# LEOPAD.net
KiCad netlist of a schematic drawn in EAGLE
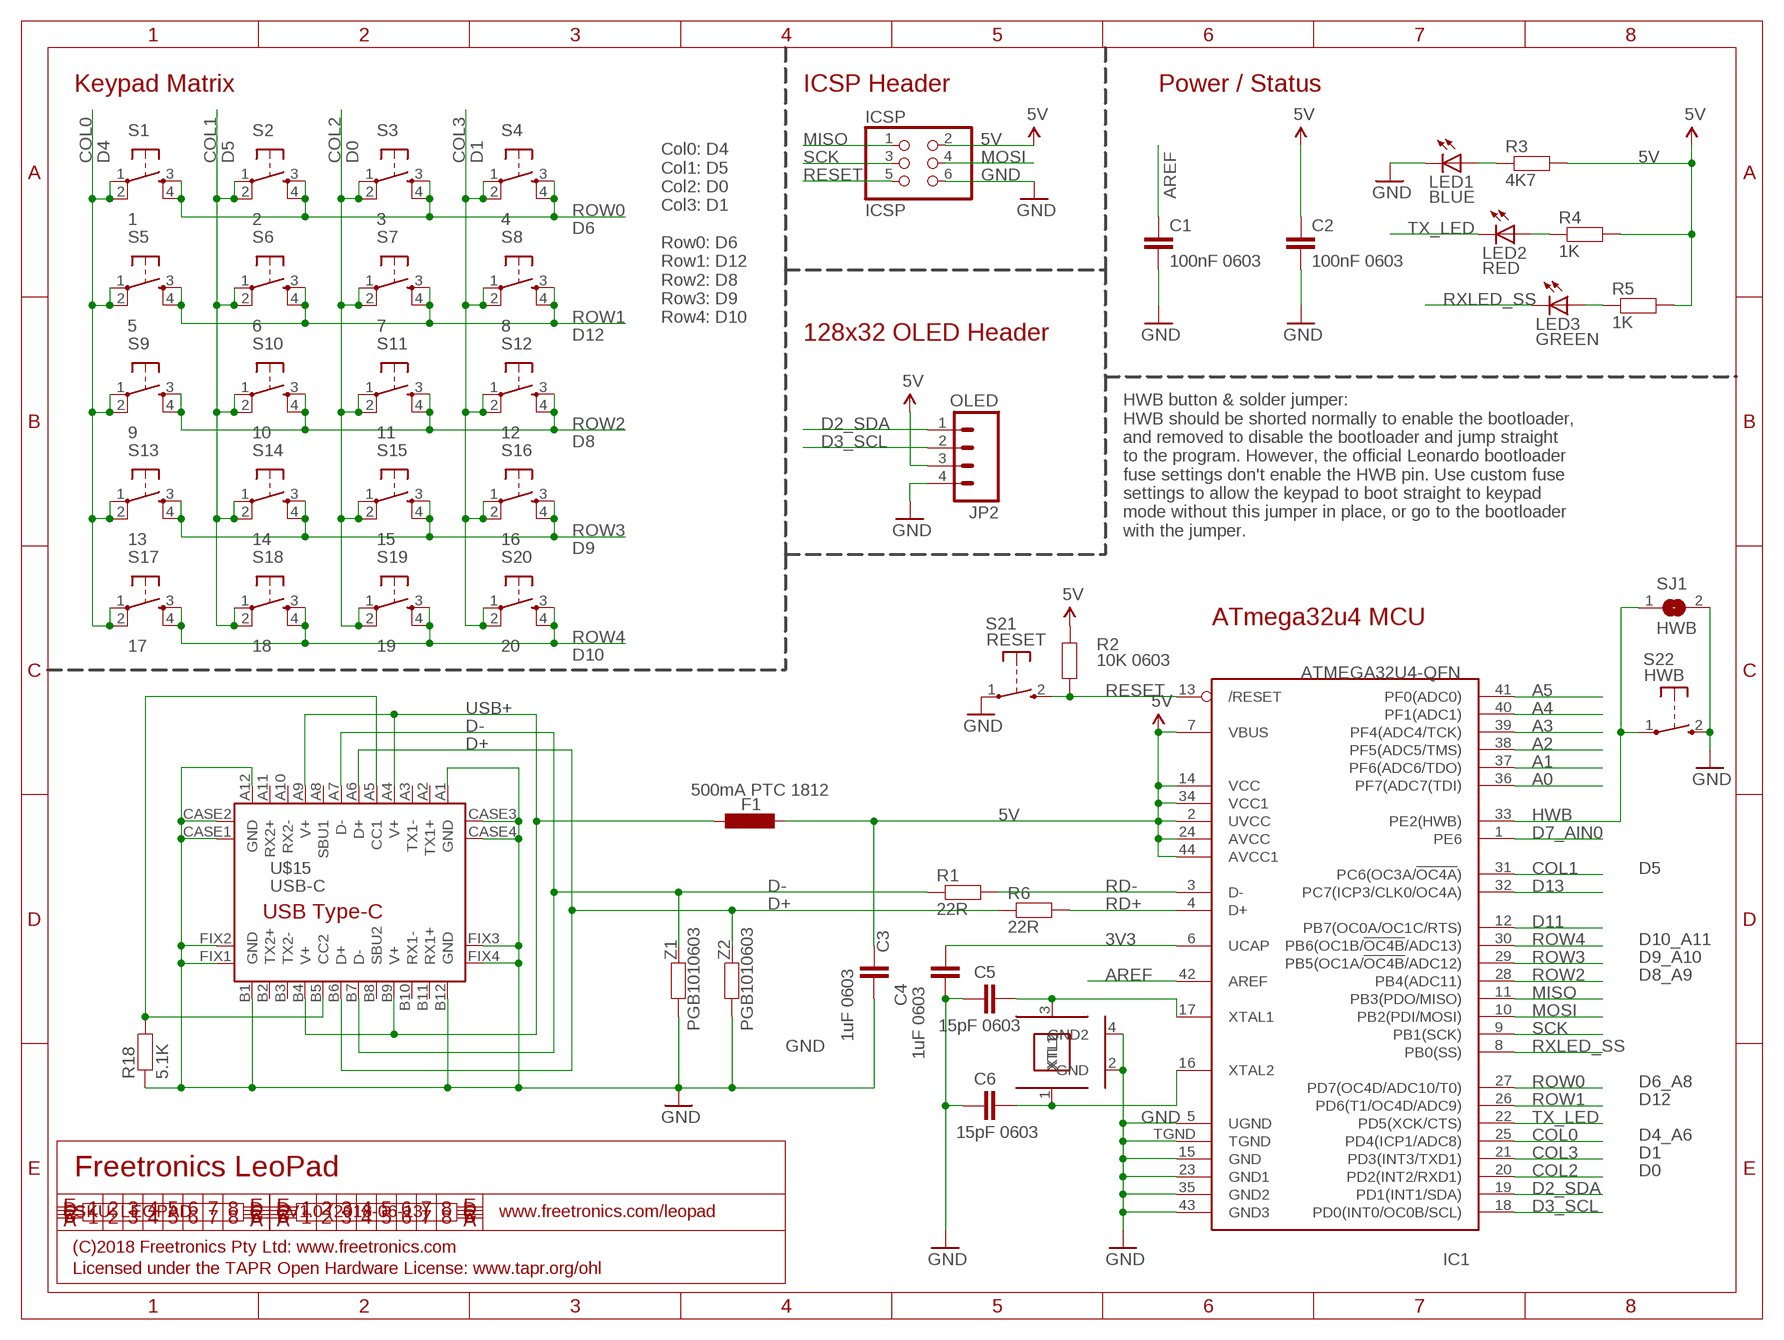
[diagram p0: schematic, sheet 1]

(export (version "E")
  (design (tool "Eeschema 10.0.6"))
  (components
    (comp (ref "C1")
      (value "100nF 0603")
      (footprint "eagle-import:0603")
      (libsource (lib "eagle-import") (part "CAP0603"))
    )
    (comp (ref "C2")
      (value "100nF 0603")
      (footprint "eagle-import:0603")
      (libsource (lib "eagle-import") (part "CAP0603"))
    )
    (comp (ref "C3")
      (value "1uF 0603")
      (footprint "eagle-import:0603")
      (libsource (lib "eagle-import") (part "CAP0603"))
    )
    (comp (ref "C4")
      (value "1uF 0603")
      (footprint "eagle-import:0603")
      (libsource (lib "eagle-import") (part "CAP0603"))
    )
    (comp (ref "C5")
      (value "15pF 0603")
      (footprint "eagle-import:0603")
      (libsource (lib "eagle-import") (part "CAP0603"))
    )
    (comp (ref "C6")
      (value "15pF 0603")
      (footprint "eagle-import:0603")
      (libsource (lib "eagle-import") (part "CAP0603"))
    )
    (comp (ref "F1")
      (value "500mA PTC 1812")
      (footprint "eagle-import:L1812")
      (libsource (lib "eagle-import") (part "L-EUL1812"))
    )
    (comp (ref "IC1")
      (value "ATMEGA32U4-QFN")
      (footprint "eagle-import:QFN-44N")
      (libsource (lib "eagle-import") (part "ATMEGA32U4-QFN"))
    )
    (comp (ref "ICSP")
      (value "ICSP")
      (footprint "eagle-import:2X03")
      (libsource (lib "eagle-import") (part "PINHD-2X3"))
    )
    (comp (ref "JP2")
      (value "OLED")
      (footprint "eagle-import:1X04")
      (libsource (lib "eagle-import") (part "M04PTH"))
    )
    (comp (ref "LED1")
      (value "BLUE")
      (footprint "eagle-import:LED-0603")
      (libsource (lib "eagle-import") (part "LED0603"))
    )
    (comp (ref "LED2")
      (value "RED")
      (footprint "eagle-import:LED-0603")
      (libsource (lib "eagle-import") (part "LED0603"))
    )
    (comp (ref "LED3")
      (value "GREEN")
      (footprint "eagle-import:LED-0603")
      (libsource (lib "eagle-import") (part "LED0603"))
    )
    (comp (ref "R1")
      (value "22R")
      (footprint "eagle-import:0603")
      (libsource (lib "eagle-import") (part "RESISTOR0603"))
    )
    (comp (ref "R2")
      (value "10K 0603")
      (footprint "eagle-import:0603")
      (libsource (lib "eagle-import") (part "freetronics-master-v1.1_RESISTOR0603"))
    )
    (comp (ref "R3")
      (value "4K7")
      (footprint "eagle-import:0603")
      (libsource (lib "eagle-import") (part "RESISTOR0603"))
    )
    (comp (ref "R4")
      (value "1K")
      (footprint "eagle-import:0603")
      (libsource (lib "eagle-import") (part "RESISTOR0603"))
    )
    (comp (ref "R5")
      (value "1K")
      (footprint "eagle-import:0603")
      (libsource (lib "eagle-import") (part "RESISTOR0603"))
    )
    (comp (ref "R6")
      (value "22R")
      (footprint "eagle-import:0603")
      (libsource (lib "eagle-import") (part "RESISTOR0603"))
    )
    (comp (ref "R18")
      (value "5.1K")
      (footprint "eagle-import:0603")
      (libsource (lib "eagle-import") (part "freetronics-original_RESISTOR0603"))
    )
    (comp (ref "S1")
      (value "1")
      (footprint "eagle-import:TACTILE-PTH-12MM")
      (libsource (lib "eagle-import") (part "TAC_SWITCH12"))
    )
    (comp (ref "S2")
      (value "2")
      (footprint "eagle-import:TACTILE-PTH-12MM")
      (libsource (lib "eagle-import") (part "TAC_SWITCH12"))
    )
    (comp (ref "S3")
      (value "3")
      (footprint "eagle-import:TACTILE-PTH-12MM")
      (libsource (lib "eagle-import") (part "TAC_SWITCH12"))
    )
    (comp (ref "S4")
      (value "4")
      (footprint "eagle-import:TACTILE-PTH-12MM")
      (libsource (lib "eagle-import") (part "TAC_SWITCH12"))
    )
    (comp (ref "S5")
      (value "5")
      (footprint "eagle-import:TACTILE-PTH-12MM")
      (libsource (lib "eagle-import") (part "TAC_SWITCH12"))
    )
    (comp (ref "S6")
      (value "6")
      (footprint "eagle-import:TACTILE-PTH-12MM")
      (libsource (lib "eagle-import") (part "TAC_SWITCH12"))
    )
    (comp (ref "S7")
      (value "7")
      (footprint "eagle-import:TACTILE-PTH-12MM")
      (libsource (lib "eagle-import") (part "TAC_SWITCH12"))
    )
    (comp (ref "S8")
      (value "8")
      (footprint "eagle-import:TACTILE-PTH-12MM")
      (libsource (lib "eagle-import") (part "TAC_SWITCH12"))
    )
    (comp (ref "S9")
      (value "9")
      (footprint "eagle-import:TACTILE-PTH-12MM")
      (libsource (lib "eagle-import") (part "TAC_SWITCH12"))
    )
    (comp (ref "S10")
      (value "10")
      (footprint "eagle-import:TACTILE-PTH-12MM")
      (libsource (lib "eagle-import") (part "TAC_SWITCH12"))
    )
    (comp (ref "S11")
      (value "11")
      (footprint "eagle-import:TACTILE-PTH-12MM")
      (libsource (lib "eagle-import") (part "TAC_SWITCH12"))
    )
    (comp (ref "S12")
      (value "12")
      (footprint "eagle-import:TACTILE-PTH-12MM")
      (libsource (lib "eagle-import") (part "TAC_SWITCH12"))
    )
    (comp (ref "S13")
      (value "13")
      (footprint "eagle-import:TACTILE-PTH-12MM")
      (libsource (lib "eagle-import") (part "TAC_SWITCH12"))
    )
    (comp (ref "S14")
      (value "14")
      (footprint "eagle-import:TACTILE-PTH-12MM")
      (libsource (lib "eagle-import") (part "TAC_SWITCH12"))
    )
    (comp (ref "S15")
      (value "15")
      (footprint "eagle-import:TACTILE-PTH-12MM")
      (libsource (lib "eagle-import") (part "TAC_SWITCH12"))
    )
    (comp (ref "S16")
      (value "16")
      (footprint "eagle-import:TACTILE-PTH-12MM")
      (libsource (lib "eagle-import") (part "TAC_SWITCH12"))
    )
    (comp (ref "S17")
      (value "17")
      (footprint "eagle-import:TACTILE-PTH-12MM")
      (libsource (lib "eagle-import") (part "TAC_SWITCH12"))
    )
    (comp (ref "S18")
      (value "18")
      (footprint "eagle-import:TACTILE-PTH-12MM")
      (libsource (lib "eagle-import") (part "TAC_SWITCH12"))
    )
    (comp (ref "S19")
      (value "19")
      (footprint "eagle-import:TACTILE-PTH-12MM")
      (libsource (lib "eagle-import") (part "TAC_SWITCH12"))
    )
    (comp (ref "S20")
      (value "20")
      (footprint "eagle-import:TACTILE-PTH-12MM")
      (libsource (lib "eagle-import") (part "TAC_SWITCH12"))
    )
    (comp (ref "S21")
      (value "RESET")
      (footprint "eagle-import:TACTILE_SWITCH_SMD_2PIN_TINY")
      (libsource (lib "eagle-import") (part "TAC_SWITCH_2PINSMT"))
    )
    (comp (ref "S22")
      (value "HWB")
      (footprint "eagle-import:TACTILE_SWITCH_SMD_2PIN_TINY")
      (libsource (lib "eagle-import") (part "TAC_SWITCH_2PINSMT"))
    )
    (comp (ref "SJ1")
      (value "HWB")
      (footprint "eagle-import:SJ")
      (libsource (lib "eagle-import") (part "SJN"))
    )
    (comp (ref "U$15")
      (value "USB-C")
      (footprint "eagle-import:USB-C-U52A")
      (libsource (lib "eagle-import") (part "USB-C"))
    )
    (comp (ref "XTL1")
      (value "16MHz")
      (footprint "eagle-import:CRYSTAL-SMD-3X2")
      (libsource (lib "eagle-import") (part "CRYSTAL-GND3X2"))
    )
    (comp (ref "Z1")
      (value "PGB1010603")
      (footprint "eagle-import:0603")
      (libsource (lib "eagle-import") (part "freetronics-master-v1.1_RESISTOR0603"))
    )
    (comp (ref "Z2")
      (value "PGB1010603")
      (footprint "eagle-import:0603")
      (libsource (lib "eagle-import") (part "freetronics-master-v1.1_RESISTOR0603"))
    )
  )
  (nets
    (net (code "1") (name "/3V3") (class "Default")
      (node (ref "C4") (pin "2") (pinfunction "2_2") (pintype "passive"))
      (node (ref "IC1") (pin "6") (pinfunction "UCAP_6") (pintype "bidirectional"))
    )
    (net (code "2") (name "/A0") (class "Default")
      (node (ref "IC1") (pin "36") (pinfunction "PF7(ADC7(TDI)_36") (pintype "bidirectional"))
    )
    (net (code "3") (name "/A1") (class "Default")
      (node (ref "IC1") (pin "37") (pinfunction "PF6(ADC6/TDO)_37") (pintype "bidirectional"))
    )
    (net (code "4") (name "/A2") (class "Default")
      (node (ref "IC1") (pin "38") (pinfunction "PF5(ADC5/TMS)_38") (pintype "bidirectional"))
    )
    (net (code "5") (name "/A3") (class "Default")
      (node (ref "IC1") (pin "39") (pinfunction "PF4(ADC4/TCK)_39") (pintype "bidirectional"))
    )
    (net (code "6") (name "/A4") (class "Default")
      (node (ref "IC1") (pin "40") (pinfunction "PF1(ADC1)_40") (pintype "bidirectional"))
    )
    (net (code "7") (name "/A5") (class "Default")
      (node (ref "IC1") (pin "41") (pinfunction "PF0(ADC0)_41") (pintype "bidirectional"))
    )
    (net (code "8") (name "/AREF") (class "Default")
      (node (ref "C1") (pin "1") (pinfunction "1_1") (pintype "passive"))
      (node (ref "IC1") (pin "42") (pinfunction "AREF_42") (pintype "bidirectional"))
    )
    (net (code "9") (name "/COL0") (class "Default")
      (node (ref "IC1") (pin "25") (pinfunction "PD4(ICP1/ADC8)_25") (pintype "bidirectional"))
      (node (ref "S1") (pin "1") (pinfunction "1_1") (pintype "passive"))
      (node (ref "S1") (pin "2") (pinfunction "2_2") (pintype "passive"))
      (node (ref "S13") (pin "1") (pinfunction "1_1") (pintype "passive"))
      (node (ref "S13") (pin "2") (pinfunction "2_2") (pintype "passive"))
      (node (ref "S17") (pin "1") (pinfunction "1_1") (pintype "passive"))
      (node (ref "S17") (pin "2") (pinfunction "2_2") (pintype "passive"))
      (node (ref "S5") (pin "1") (pinfunction "1_1") (pintype "passive"))
      (node (ref "S5") (pin "2") (pinfunction "2_2") (pintype "passive"))
      (node (ref "S9") (pin "1") (pinfunction "1_1") (pintype "passive"))
      (node (ref "S9") (pin "2") (pinfunction "2_2") (pintype "passive"))
    )
    (net (code "10") (name "/COL1") (class "Default")
      (node (ref "IC1") (pin "31") (pinfunction "PC6(OC3A/~{OC4A})_31") (pintype "bidirectional"))
      (node (ref "S10") (pin "1") (pinfunction "1_1") (pintype "passive"))
      (node (ref "S10") (pin "2") (pinfunction "2_2") (pintype "passive"))
      (node (ref "S14") (pin "1") (pinfunction "1_1") (pintype "passive"))
      (node (ref "S14") (pin "2") (pinfunction "2_2") (pintype "passive"))
      (node (ref "S18") (pin "1") (pinfunction "1_1") (pintype "passive"))
      (node (ref "S18") (pin "2") (pinfunction "2_2") (pintype "passive"))
      (node (ref "S2") (pin "1") (pinfunction "1_1") (pintype "passive"))
      (node (ref "S2") (pin "2") (pinfunction "2_2") (pintype "passive"))
      (node (ref "S6") (pin "1") (pinfunction "1_1") (pintype "passive"))
      (node (ref "S6") (pin "2") (pinfunction "2_2") (pintype "passive"))
    )
    (net (code "11") (name "/COL2") (class "Default")
      (node (ref "IC1") (pin "20") (pinfunction "PD2(INT2/RXD1)_20") (pintype "bidirectional"))
      (node (ref "S11") (pin "1") (pinfunction "1_1") (pintype "passive"))
      (node (ref "S11") (pin "2") (pinfunction "2_2") (pintype "passive"))
      (node (ref "S15") (pin "1") (pinfunction "1_1") (pintype "passive"))
      (node (ref "S15") (pin "2") (pinfunction "2_2") (pintype "passive"))
      (node (ref "S19") (pin "1") (pinfunction "1_1") (pintype "passive"))
      (node (ref "S19") (pin "2") (pinfunction "2_2") (pintype "passive"))
      (node (ref "S3") (pin "1") (pinfunction "1_1") (pintype "passive"))
      (node (ref "S3") (pin "2") (pinfunction "2_2") (pintype "passive"))
      (node (ref "S7") (pin "1") (pinfunction "1_1") (pintype "passive"))
      (node (ref "S7") (pin "2") (pinfunction "2_2") (pintype "passive"))
    )
    (net (code "12") (name "/COL3") (class "Default")
      (node (ref "IC1") (pin "21") (pinfunction "PD3(INT3/TXD1)_21") (pintype "bidirectional"))
      (node (ref "S12") (pin "1") (pinfunction "1_1") (pintype "passive"))
      (node (ref "S12") (pin "2") (pinfunction "2_2") (pintype "passive"))
      (node (ref "S16") (pin "1") (pinfunction "1_1") (pintype "passive"))
      (node (ref "S16") (pin "2") (pinfunction "2_2") (pintype "passive"))
      (node (ref "S20") (pin "1") (pinfunction "1_1") (pintype "passive"))
      (node (ref "S20") (pin "2") (pinfunction "2_2") (pintype "passive"))
      (node (ref "S4") (pin "1") (pinfunction "1_1") (pintype "passive"))
      (node (ref "S4") (pin "2") (pinfunction "2_2") (pintype "passive"))
      (node (ref "S8") (pin "1") (pinfunction "1_1") (pintype "passive"))
      (node (ref "S8") (pin "2") (pinfunction "2_2") (pintype "passive"))
    )
    (net (code "13") (name "/D+") (class "Default")
      (node (ref "R6") (pin "1") (pinfunction "1_1") (pintype "passive"))
      (node (ref "U$15") (pin "A6") (pinfunction "D+_A6") (pintype "bidirectional"))
      (node (ref "U$15") (pin "B6") (pinfunction "D+_B6") (pintype "bidirectional"))
      (node (ref "Z2") (pin "2") (pinfunction "2_2") (pintype "passive"))
    )
    (net (code "14") (name "/D-") (class "Default")
      (node (ref "R1") (pin "1") (pinfunction "1_1") (pintype "passive"))
      (node (ref "U$15") (pin "A7") (pinfunction "D-_A7") (pintype "bidirectional"))
      (node (ref "U$15") (pin "B7") (pinfunction "D-_B7") (pintype "bidirectional"))
      (node (ref "Z1") (pin "2") (pinfunction "2_2") (pintype "passive"))
    )
    (net (code "15") (name "/D2_SDA") (class "Default")
      (node (ref "IC1") (pin "19") (pinfunction "PD1(INT1/SDA)_19") (pintype "bidirectional"))
      (node (ref "JP2") (pin "1") (pinfunction "1_1") (pintype "passive"))
    )
    (net (code "16") (name "/D3_SCL") (class "Default")
      (node (ref "IC1") (pin "18") (pinfunction "PD0(INT0/OC0B/SCL)_18") (pintype "bidirectional"))
      (node (ref "JP2") (pin "2") (pinfunction "2_2") (pintype "passive"))
    )
    (net (code "17") (name "/D7_AIN0") (class "Default")
      (node (ref "IC1") (pin "1") (pinfunction "PE6_1") (pintype "bidirectional"))
    )
    (net (code "18") (name "/D11") (class "Default")
      (node (ref "IC1") (pin "12") (pinfunction "PB7(OC0A/OC1C/RTS)_12") (pintype "bidirectional"))
    )
    (net (code "19") (name "/D13") (class "Default")
      (node (ref "IC1") (pin "32") (pinfunction "PC7(ICP3/CLK0/OC4A)_32") (pintype "bidirectional"))
    )
    (net (code "20") (name "/HWB") (class "Default")
      (node (ref "IC1") (pin "33") (pinfunction "PE2(HWB)_33") (pintype "bidirectional"))
      (node (ref "S22") (pin "1") (pinfunction "P_1") (pintype "passive"))
      (node (ref "SJ1") (pin "1") (pinfunction "1_1") (pintype "passive"))
    )
    (net (code "21") (name "/MISO") (class "Default")
      (node (ref "IC1") (pin "11") (pinfunction "PB3(PDO/MISO)_11") (pintype "bidirectional"))
      (node (ref "ICSP") (pin "1") (pinfunction "1_1") (pintype "passive"))
    )
    (net (code "22") (name "/MOSI") (class "Default")
      (node (ref "IC1") (pin "10") (pinfunction "PB2(PDI/MOSI)_10") (pintype "bidirectional"))
      (node (ref "ICSP") (pin "4") (pinfunction "4_4") (pintype "passive"))
    )
    (net (code "23") (name "/RD+") (class "Default")
      (node (ref "IC1") (pin "4") (pinfunction "D+_4") (pintype "bidirectional"))
      (node (ref "R6") (pin "2") (pinfunction "2_2") (pintype "passive"))
    )
    (net (code "24") (name "/RD-") (class "Default")
      (node (ref "IC1") (pin "3") (pinfunction "D-_3") (pintype "bidirectional"))
      (node (ref "R1") (pin "2") (pinfunction "2_2") (pintype "passive"))
    )
    (net (code "25") (name "/RESET") (class "Default")
      (node (ref "IC1") (pin "13") (pinfunction "/RESET_13") (pintype "bidirectional"))
      (node (ref "ICSP") (pin "5") (pinfunction "5_5") (pintype "passive"))
      (node (ref "R2") (pin "1") (pinfunction "1_1") (pintype "passive"))
      (node (ref "S21") (pin "2") (pinfunction "S_2") (pintype "passive"))
    )
    (net (code "26") (name "/ROW0") (class "Default")
      (node (ref "IC1") (pin "27") (pinfunction "PD7(OC4D/ADC10/T0)_27") (pintype "bidirectional"))
      (node (ref "S1") (pin "3") (pinfunction "3_3") (pintype "passive"))
      (node (ref "S1") (pin "4") (pinfunction "4_4") (pintype "passive"))
      (node (ref "S2") (pin "3") (pinfunction "3_3") (pintype "passive"))
      (node (ref "S2") (pin "4") (pinfunction "4_4") (pintype "passive"))
      (node (ref "S3") (pin "3") (pinfunction "3_3") (pintype "passive"))
      (node (ref "S3") (pin "4") (pinfunction "4_4") (pintype "passive"))
      (node (ref "S4") (pin "3") (pinfunction "3_3") (pintype "passive"))
      (node (ref "S4") (pin "4") (pinfunction "4_4") (pintype "passive"))
    )
    (net (code "27") (name "/ROW1") (class "Default")
      (node (ref "IC1") (pin "26") (pinfunction "PD6(T1/OC4D/ADC9)_26") (pintype "bidirectional"))
      (node (ref "S5") (pin "3") (pinfunction "3_3") (pintype "passive"))
      (node (ref "S5") (pin "4") (pinfunction "4_4") (pintype "passive"))
      (node (ref "S6") (pin "3") (pinfunction "3_3") (pintype "passive"))
      (node (ref "S6") (pin "4") (pinfunction "4_4") (pintype "passive"))
      (node (ref "S7") (pin "3") (pinfunction "3_3") (pintype "passive"))
      (node (ref "S7") (pin "4") (pinfunction "4_4") (pintype "passive"))
      (node (ref "S8") (pin "3") (pinfunction "3_3") (pintype "passive"))
      (node (ref "S8") (pin "4") (pinfunction "4_4") (pintype "passive"))
    )
    (net (code "28") (name "/ROW2") (class "Default")
      (node (ref "IC1") (pin "28") (pinfunction "PB4(ADC11)_28") (pintype "bidirectional"))
      (node (ref "S10") (pin "3") (pinfunction "3_3") (pintype "passive"))
      (node (ref "S10") (pin "4") (pinfunction "4_4") (pintype "passive"))
      (node (ref "S11") (pin "3") (pinfunction "3_3") (pintype "passive"))
      (node (ref "S11") (pin "4") (pinfunction "4_4") (pintype "passive"))
      (node (ref "S12") (pin "3") (pinfunction "3_3") (pintype "passive"))
      (node (ref "S12") (pin "4") (pinfunction "4_4") (pintype "passive"))
      (node (ref "S9") (pin "3") (pinfunction "3_3") (pintype "passive"))
      (node (ref "S9") (pin "4") (pinfunction "4_4") (pintype "passive"))
    )
    (net (code "29") (name "/ROW3") (class "Default")
      (node (ref "IC1") (pin "29") (pinfunction "PB5(OC1A/~{OC4B}/ADC12)_29") (pintype "bidirectional"))
      (node (ref "S13") (pin "3") (pinfunction "3_3") (pintype "passive"))
      (node (ref "S13") (pin "4") (pinfunction "4_4") (pintype "passive"))
      (node (ref "S14") (pin "3") (pinfunction "3_3") (pintype "passive"))
      (node (ref "S14") (pin "4") (pinfunction "4_4") (pintype "passive"))
      (node (ref "S15") (pin "3") (pinfunction "3_3") (pintype "passive"))
      (node (ref "S15") (pin "4") (pinfunction "4_4") (pintype "passive"))
      (node (ref "S16") (pin "3") (pinfunction "3_3") (pintype "passive"))
      (node (ref "S16") (pin "4") (pinfunction "4_4") (pintype "passive"))
    )
    (net (code "30") (name "/ROW4") (class "Default")
      (node (ref "IC1") (pin "30") (pinfunction "PB6(OC1B/~{OC4B}/ADC13)_30") (pintype "bidirectional"))
      (node (ref "S17") (pin "3") (pinfunction "3_3") (pintype "passive"))
      (node (ref "S17") (pin "4") (pinfunction "4_4") (pintype "passive"))
      (node (ref "S18") (pin "3") (pinfunction "3_3") (pintype "passive"))
      (node (ref "S18") (pin "4") (pinfunction "4_4") (pintype "passive"))
      (node (ref "S19") (pin "3") (pinfunction "3_3") (pintype "passive"))
      (node (ref "S19") (pin "4") (pinfunction "4_4") (pintype "passive"))
      (node (ref "S20") (pin "3") (pinfunction "3_3") (pintype "passive"))
      (node (ref "S20") (pin "4") (pinfunction "4_4") (pintype "passive"))
    )
    (net (code "31") (name "/RXLED_SS") (class "Default")
      (node (ref "IC1") (pin "8") (pinfunction "PB0(SS)_8") (pintype "bidirectional"))
      (node (ref "LED3") (pin "C") (pinfunction "C_C") (pintype "passive"))
    )
    (net (code "32") (name "/SCK") (class "Default")
      (node (ref "IC1") (pin "9") (pinfunction "PB1(SCK)_9") (pintype "bidirectional"))
      (node (ref "ICSP") (pin "3") (pinfunction "3_3") (pintype "passive"))
    )
    (net (code "33") (name "/TX_LED") (class "Default")
      (node (ref "IC1") (pin "22") (pinfunction "PD5(XCK/CTS)_22") (pintype "bidirectional"))
      (node (ref "LED2") (pin "C") (pinfunction "C_C") (pintype "passive"))
    )
    (net (code "34") (name "/USB+") (class "Default")
      (node (ref "F1") (pin "1") (pinfunction "1_1") (pintype "passive"))
      (node (ref "U$15") (pin "A4") (pinfunction "V+_A4") (pintype "power_in"))
      (node (ref "U$15") (pin "A9") (pinfunction "V+_A9") (pintype "power_in"))
      (node (ref "U$15") (pin "B4") (pinfunction "V+_B4") (pintype "power_in"))
      (node (ref "U$15") (pin "B9") (pinfunction "V+_B9") (pintype "power_in"))
    )
    (net (code "35") (name "5V") (class "Default")
      (node (ref "C2") (pin "1") (pinfunction "1_1") (pintype "passive"))
      (node (ref "C3") (pin "1") (pinfunction "1_1") (pintype "passive"))
      (node (ref "F1") (pin "2") (pinfunction "2_2") (pintype "passive"))
      (node (ref "IC1") (pin "14") (pinfunction "VCC_14") (pintype "bidirectional"))
      (node (ref "IC1") (pin "2") (pinfunction "UVCC_2") (pintype "bidirectional"))
      (node (ref "IC1") (pin "24") (pinfunction "AVCC_24") (pintype "bidirectional"))
      (node (ref "IC1") (pin "34") (pinfunction "VCC1_34") (pintype "bidirectional"))
      (node (ref "IC1") (pin "44") (pinfunction "AVCC1_44") (pintype "bidirectional"))
      (node (ref "IC1") (pin "7") (pinfunction "VBUS_7") (pintype "bidirectional"))
      (node (ref "ICSP") (pin "2") (pinfunction "2_2") (pintype "passive"))
      (node (ref "JP2") (pin "3") (pinfunction "3_3") (pintype "passive"))
      (node (ref "R2") (pin "2") (pinfunction "2_2") (pintype "passive"))
      (node (ref "R3") (pin "2") (pinfunction "2_2") (pintype "passive"))
      (node (ref "R4") (pin "2") (pinfunction "2_2") (pintype "passive"))
      (node (ref "R5") (pin "2") (pinfunction "2_2") (pintype "passive"))
    )
    (net (code "36") (name "GND") (class "Default")
      (node (ref "C1") (pin "2") (pinfunction "2_2") (pintype "passive"))
      (node (ref "C2") (pin "2") (pinfunction "2_2") (pintype "passive"))
      (node (ref "C3") (pin "2") (pinfunction "2_2") (pintype "passive"))
      (node (ref "C4") (pin "1") (pinfunction "1_1") (pintype "passive"))
      (node (ref "C5") (pin "1") (pinfunction "1_1") (pintype "passive"))
      (node (ref "C6") (pin "1") (pinfunction "1_1") (pintype "passive"))
      (node (ref "IC1") (pin "15") (pinfunction "GND_15") (pintype "bidirectional"))
      (node (ref "IC1") (pin "23") (pinfunction "GND1_23") (pintype "bidirectional"))
      (node (ref "IC1") (pin "35") (pinfunction "GND2_35") (pintype "bidirectional"))
      (node (ref "IC1") (pin "43") (pinfunction "GND3_43") (pintype "bidirectional"))
      (node (ref "IC1") (pin "5") (pinfunction "UGND_5") (pintype "bidirectional"))
      (node (ref "IC1") (pin "TGND") (pinfunction "TGND_TGND") (pintype "bidirectional"))
      (node (ref "ICSP") (pin "6") (pinfunction "6_6") (pintype "passive"))
      (node (ref "JP2") (pin "4") (pinfunction "4_4") (pintype "passive"))
      (node (ref "LED1") (pin "C") (pinfunction "C_C") (pintype "passive"))
      (node (ref "R18") (pin "1") (pinfunction "1_1") (pintype "passive"))
      (node (ref "S21") (pin "1") (pinfunction "P_1") (pintype "passive"))
      (node (ref "S22") (pin "2") (pinfunction "S_2") (pintype "passive"))
      (node (ref "SJ1") (pin "2") (pinfunction "2_2") (pintype "passive"))
      (node (ref "U$15") (pin "A1") (pinfunction "GND_A1") (pintype "power_in"))
      (node (ref "U$15") (pin "A12") (pinfunction "GND_A12") (pintype "power_in"))
      (node (ref "U$15") (pin "B1") (pinfunction "GND_B1") (pintype "power_in"))
      (node (ref "U$15") (pin "B12") (pinfunction "GND_B12") (pintype "power_in"))
      (node (ref "U$15") (pin "CASE1") (pinfunction "GND_CASE1") (pintype "power_in"))
      (node (ref "U$15") (pin "CASE2") (pinfunction "GND_CASE2") (pintype "power_in"))
      (node (ref "U$15") (pin "CASE3") (pinfunction "GND_CASE3") (pintype "power_in"))
      (node (ref "U$15") (pin "CASE4") (pinfunction "GND_CASE4") (pintype "power_in"))
      (node (ref "U$15") (pin "FIX1") (pinfunction "GND_FIX1") (pintype "power_in"))
      (node (ref "U$15") (pin "FIX2") (pinfunction "GND_FIX2") (pintype "power_in"))
      (node (ref "U$15") (pin "FIX3") (pinfunction "GND_FIX3") (pintype "power_in"))
      (node (ref "U$15") (pin "FIX4") (pinfunction "GND_FIX4") (pintype "power_in"))
      (node (ref "XTL1") (pin "2") (pinfunction "GND_2") (pintype "bidirectional"))
      (node (ref "XTL1") (pin "4") (pinfunction "GND2_4") (pintype "bidirectional"))
      (node (ref "Z1") (pin "1") (pinfunction "1_1") (pintype "passive"))
      (node (ref "Z2") (pin "1") (pinfunction "1_1") (pintype "passive"))
    )
    (net (code "37") (name "Net-(IC1-XTAL1)") (class "Default")
      (node (ref "C5") (pin "2") (pinfunction "2_2") (pintype "passive"))
      (node (ref "IC1") (pin "17") (pinfunction "XTAL1_17") (pintype "bidirectional"))
      (node (ref "XTL1") (pin "3") (pinfunction "XTL2_3") (pintype "bidirectional"))
    )
    (net (code "38") (name "Net-(IC1-XTAL2)") (class "Default")
      (node (ref "C6") (pin "2") (pinfunction "2_2") (pintype "passive"))
      (node (ref "IC1") (pin "16") (pinfunction "XTAL2_16") (pintype "bidirectional"))
      (node (ref "XTL1") (pin "1") (pinfunction "XTL1_1") (pintype "bidirectional"))
    )
    (net (code "39") (name "Net-(LED1-PadA)") (class "Default")
      (node (ref "LED1") (pin "A") (pinfunction "A_A") (pintype "passive"))
      (node (ref "R3") (pin "1") (pinfunction "1_1") (pintype "passive"))
    )
    (net (code "40") (name "Net-(LED2-PadA)") (class "Default")
      (node (ref "LED2") (pin "A") (pinfunction "A_A") (pintype "passive"))
      (node (ref "R4") (pin "1") (pinfunction "1_1") (pintype "passive"))
    )
    (net (code "41") (name "Net-(LED3-PadA)") (class "Default")
      (node (ref "LED3") (pin "A") (pinfunction "A_A") (pintype "passive"))
      (node (ref "R5") (pin "1") (pinfunction "1_1") (pintype "passive"))
    )
    (net (code "42") (name "Net-(U$15-CC1)") (class "Default")
      (node (ref "R18") (pin "2") (pinfunction "2_2") (pintype "passive"))
      (node (ref "U$15") (pin "A5") (pinfunction "CC1_A5") (pintype "bidirectional"))
      (node (ref "U$15") (pin "B5") (pinfunction "CC2_B5") (pintype "bidirectional"))
    )
    (net (code "43") (name "unconnected-(U$15-RX1+-PadB11)") (class "Default")
      (node (ref "U$15") (pin "B11") (pinfunction "RX1+_B11") (pintype "bidirectional"))
    )
    (net (code "44") (name "unconnected-(U$15-RX1--PadB10)") (class "Default")
      (node (ref "U$15") (pin "B10") (pinfunction "RX1-_B10") (pintype "bidirectional"))
    )
    (net (code "45") (name "unconnected-(U$15-RX2+-PadA11)") (class "Default")
      (node (ref "U$15") (pin "A11") (pinfunction "RX2+_A11") (pintype "bidirectional"))
    )
    (net (code "46") (name "unconnected-(U$15-RX2--PadA10)") (class "Default")
      (node (ref "U$15") (pin "A10") (pinfunction "RX2-_A10") (pintype "bidirectional"))
    )
    (net (code "47") (name "unconnected-(U$15-SBU1-PadA8)") (class "Default")
      (node (ref "U$15") (pin "A8") (pinfunction "SBU1_A8") (pintype "bidirectional"))
    )
    (net (code "48") (name "unconnected-(U$15-SBU2-PadB8)") (class "Default")
      (node (ref "U$15") (pin "B8") (pinfunction "SBU2_B8") (pintype "bidirectional"))
    )
    (net (code "49") (name "unconnected-(U$15-TX1+-PadA2)") (class "Default")
      (node (ref "U$15") (pin "A2") (pinfunction "TX1+_A2") (pintype "bidirectional"))
    )
    (net (code "50") (name "unconnected-(U$15-TX1--PadA3)") (class "Default")
      (node (ref "U$15") (pin "A3") (pinfunction "TX1-_A3") (pintype "bidirectional"))
    )
    (net (code "51") (name "unconnected-(U$15-TX2+-PadB2)") (class "Default")
      (node (ref "U$15") (pin "B2") (pinfunction "TX2+_B2") (pintype "bidirectional"))
    )
    (net (code "52") (name "unconnected-(U$15-TX2--PadB3)") (class "Default")
      (node (ref "U$15") (pin "B3") (pinfunction "TX2-_B3") (pintype "bidirectional"))
    )
  )
)
